# power-supply.net
KiCad netlist of a schematic drawn in Altium Designer
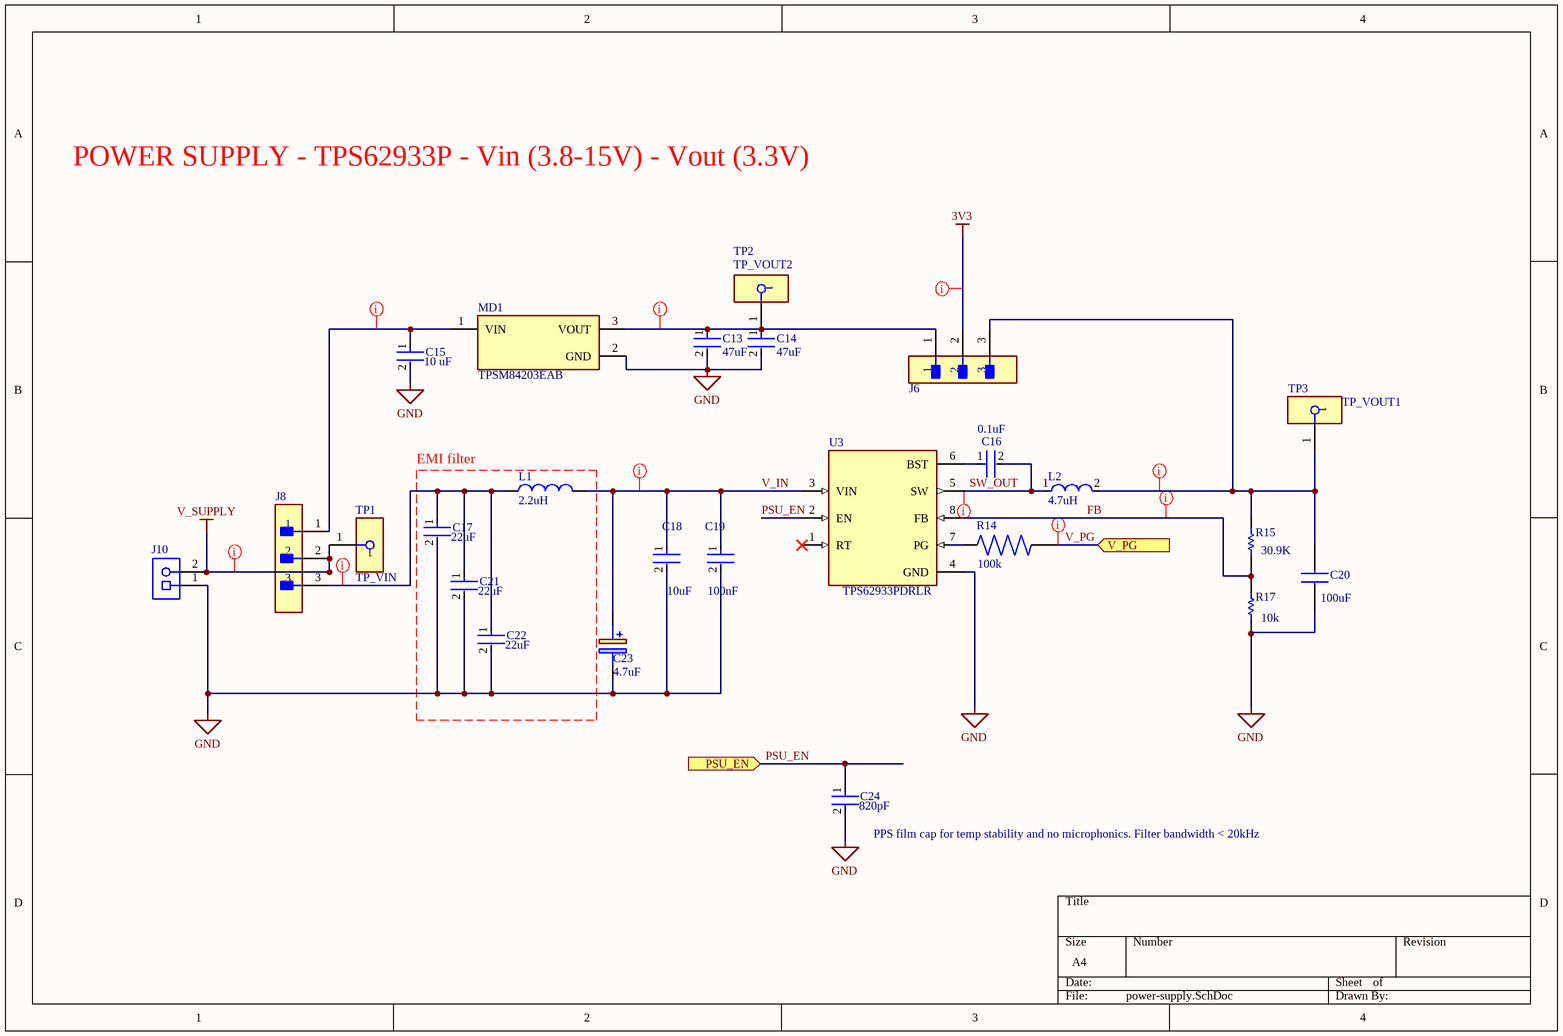
[diagram p0: power-supply.SchDoc]

(export (version "E")
  (design (tool "Eeschema 10.0.6"))
  (components
    (comp (ref "C13")
      (value "47uF")
      (footprint "FP-C3216-160-0_2-MFG")
      (description "Multilayer Ceramic Capacitors 47uF ±20% 25V X5R SMD 1206")
      (fields (field (name "VOLTAGE") "25V") (field (name "TOLERANCE") "20%"))
      (libsource (lib "Altium Content Vault") (part "11868f565c42a9108669ba33697ecf6"))
    )
    (comp (ref "C14")
      (value "47uF")
      (footprint "FP-C3216-160-0_2-MFG")
      (description "Multilayer Ceramic Capacitors 47uF ±20% 25V X5R SMD 1206")
      (fields (field (name "VOLTAGE") "25V") (field (name "TOLERANCE") "20%"))
      (libsource (lib "Altium Content Vault") (part "11868f565c42a9108669ba33697ecf6"))
    )
    (comp (ref "C15")
      (value "10 uF")
      (footprint "FP-GRT31C-0_2-IPC_A")
      (description "Multi-Layer Ceramic Capacitor 10uF 50V X5R ±10% 1206 Emboss T/R")
      (fields (field (name "TOLERANCE") "10%"))
      (libsource (lib "Altium Content Vault") (part "02cd4be3c70576c341d710602a673aa"))
    )
    (comp (ref "C16")
      (value "0.1uF")
      (footprint "FP-C0603C104Z4VACTU-MFG")
      (description "CAP CER 0.1UF 16V Y5V 0603")
      (fields (field (name "TOLERANCE") "80%"))
      (libsource (lib "Altium Content Vault") (part "b4654b650e69147ec39a6b967a45e02"))
    )
    (comp (ref "C17")
      (value "22uF")
      (footprint "FP-GRM32-MFG")
      (description "CAP CER 22UF 25V X5R 1210")
      (fields
        (field (name "TOLERANCE") "10%")
        (field (name "MANUFACTURER") "Murata Electronics North America")
      )
      (libsource (lib "Altium Content Vault") (part "11868f565c42a9108669ba33697ecf6"))
    )
    (comp (ref "C18")
      (value "10uF")
      (footprint "FP-GRM21B-0_15-IPC_A")
      (description "Chip Multilayer Ceramic Capacitors for General Purpose, 0805, 10uF, X5R, 15%, 20%, 25V")
      (fields (field (name "TOLERANCE") "20%"))
      (libsource (lib "Altium Content Vault") (part "b4654b650e69147ec39a6b967a45e02"))
    )
    (comp (ref "C19")
      (value "100nF")
      (footprint "FP-0603-L_1_6_0_15-W_0_81-MFG")
      (description "General Purpose Ceramic Capacitor, 0603, 100nF, 10%, X7R, 15%, 25V")
      (fields (field (name "VOLTAGE") "25V") (field (name "TOLERANCE") "10%"))
      (libsource (lib "Altium Content Vault") (part "02cd4be3c70576c341d710602a673aa"))
    )
    (comp (ref "C20")
      (value "100uF")
      (footprint "CAPC3225X270N")
      (fields
        (field (name "MOUSER PART NUMBER") "81-GRM32EC80J107ME0L")
        (field (name "MANUFACTURER_PART_NUMBER") "GRM32EC80J107ME20L")
      )
      (libsource (lib "GRM32EC80J107ME20L") (part "GRM32EC80J107ME20L"))
    )
    (comp (ref "C21")
      (value "22uF")
      (footprint "FP-GRM32-MFG")
      (description "CAP CER 22UF 25V X5R 1210")
      (fields
        (field (name "TOLERANCE") "10%")
        (field (name "MANUFACTURER") "Murata Electronics North America")
      )
      (libsource (lib "Altium Content Vault") (part "11868f565c42a9108669ba33697ecf6"))
    )
    (comp (ref "C22")
      (value "22uF")
      (footprint "FP-GRM32-MFG")
      (description "CAP CER 22UF 25V X5R 1210")
      (fields
        (field (name "TOLERANCE") "10%")
        (field (name "MANUFACTURER") "Murata Electronics North America")
      )
      (libsource (lib "Altium Content Vault") (part "11868f565c42a9108669ba33697ecf6"))
    )
    (comp (ref "C23")
      (value "4.7uF")
      (footprint "CAPPM3528X120N")
      (description "Cap Tant Solid 4.7uF 35V B CASE 10% (3.5 X 2.8 X 1.9mm) Inward L SMD 3528-21 0.7 Ohm 125C T/R")
      (fields
        (field (name "MOUSER PART NUMBER") "581-TPSB475K035R0700")
        (field (name "MANUFACTURER_PART_NUMBER") "TPSB475K035R0700")
      )
      (libsource (lib "TPSB475K035R0700") (part "TPSB475K035R0700"))
    )
    (comp (ref "C24")
      (value "ECH-U1H821JX5")
      (footprint "FP-ECHUJ1-MFG")
      (description "CAP FILM 820PF 5% 50VDC 0805")
      (fields
        (field (name "TOLERANCE") "5%")
        (field (name "CAPACITANCE") "820pF")
        (field (name "VOLTAGE") "50V")
      )
      (libsource (lib "Altium Content Vault") (part "b4654b650e69147ec39a6b967a45e02"))
    )
    (comp (ref "J6")
      (value "PREC003SAAN-RC")
      (footprint "FP-PREC003SAAN-RC-MFG")
      (description "PREC003SAAN-RC Conn Header Vert 3POS 2.54MM")
      (libsource (lib "Altium Content Vault") (part "0d3f023dd272f625e17a2be33dea85f"))
    )
    (comp (ref "J8")
      (value "PREC003SAAN-RC")
      (footprint "FP-PREC003SAAN-RC-MFG")
      (description "PREC003SAAN-RC Conn Header Vert 3POS 2.54MM")
      (libsource (lib "") (part "0d3f023dd272f625e17a2be33dea85f_1"))
    )
    (comp (ref "J10")
      (value "1729128")
      (footprint "PHOE-1729128-2_V")
      (description "PCB Terminal Block, 13.5 A, 400 V, 2-Pin THD, RoHS, Bulk")
      (fields (field (name "MANUFACTURER") "Phoenix Contact"))
      (libsource (lib "Altium Content Vault") (part "CN-2P-F-R2"))
    )
    (comp (ref "L1")
      (value "2.2uH")
      (footprint "WE-PMCI_1210_L3.2W2.5H1.2")
      (description "74479299222 General Purpose Inductor, 2.2uH, 15%, 1 Element, Iron Alloy-Core, SMD, 1210")
      (fields (field (name "TOLERANCE") "20%"))
      (libsource (lib "Altium Content Vault") (part "Inductor - 1"))
    )
    (comp (ref "L2")
      (value "4.7uH")
      (footprint "FP-IHLP-3232DZ-FP_2_413x5-MFG")
      (description "Commercial Inductors, Low DCR Series 4.7uH 8A 22.6mΩ 20%")
      (fields (field (name "TOLERANCE") "20%"))
      (libsource (lib "Altium Content Vault") (part "725321dda6339637d4d059423bc1c3c"))
    )
    (comp (ref "MD1")
      (value "TPSM84203EAB")
      (footprint "FP-EAB0003A-MFG")
      (description "DC DC CONVERTER 3.3V")
      (libsource (lib "Altium Content Vault") (part "495afe2ae4e3f912dabcd063790f0cb"))
    )
    (comp (ref "R14")
      (value "100k")
      (footprint "RESC1508X50N")
      (fields (field (name "MF") "Vishay") (field (name "MP") "CRCW0603100KFKEA"))
      (libsource (lib "CRCW0603100KFKEA") (part "CRCW0603100KFKEA"))
    )
    (comp (ref "R15")
      (value "30.9K")
      (footprint "RESC1608X55X25NL10T15")
      (description "Rfbt")
      (fields (field (name "MANUFACTURER") "Yageo") (field (name "PART NUMBER") "RC0603FR-0730K9L"))
      (libsource (lib "Altium Content Vault") (part "RES"))
    )
    (comp (ref "R17")
      (value "10k")
      (footprint "RESC1609X50X30NL8T20")
      (fields (field (name "MANUFACTURER") "Vishay Semiconductor"))
      (libsource (lib "Altium Content Vault") (part "RES-2"))
    )
    (comp (ref "TP1")
      (value "TP_VIN")
      (footprint "FP-5019-MFG")
      (description "V_IN_TEST")
      (libsource (lib "Altium Content Vault") (part "98815daf2f2c152b0c43f5ab9800df6"))
    )
    (comp (ref "TP2")
      (value "TP_VOUT2")
      (footprint "FP-5019-MFG")
      (libsource (lib "") (part "98815daf2f2c152b0c43f5ab9800df6_1"))
    )
    (comp (ref "TP3")
      (value "TP_VOUT1")
      (footprint "FP-5019-MFG")
      (libsource (lib "") (part "98815daf2f2c152b0c43f5ab9800df6_1"))
    )
    (comp (ref "U3")
      (value "TPS62933PDRLR")
      (footprint "SOFL50P160X60-8S")
      (libsource (lib "TPS62933PDRLR") (part "TPS62933PDRLR"))
    )
  )
  (nets
    (net (code "1") (name "/FB") (class "Default")
      (node (ref "R15") (pin "1") (pinfunction "1_1") (pintype "passive"))
      (node (ref "R17") (pin "2") (pinfunction "2_2") (pintype "passive"))
      (node (ref "U3") (pin "8") (pinfunction "FB_8") (pintype "input"))
    )
    (net (code "2") (name "/PSU_EN") (class "Default")
      (node (ref "C24") (pin "1") (pinfunction "1_1") (pintype "passive"))
      (node (ref "U3") (pin "2") (pinfunction "EN_2") (pintype "input"))
    )
    (net (code "3") (name "/SW_OUT") (class "Default")
      (node (ref "C16") (pin "2") (pinfunction "2_2") (pintype "passive"))
      (node (ref "L2") (pin "1") (pinfunction "1_1") (pintype "passive"))
      (node (ref "U3") (pin "5") (pinfunction "SW_5") (pintype "output"))
    )
    (net (code "4") (name "/V_IN") (class "Default")
      (node (ref "C18") (pin "1") (pinfunction "1_1") (pintype "passive"))
      (node (ref "C19") (pin "1") (pinfunction "1_1") (pintype "passive"))
      (node (ref "C23") (pin "1") (pinfunction "+_1") (pintype "passive"))
      (node (ref "L1") (pin "2") (pinfunction "2_2") (pintype "passive"))
      (node (ref "U3") (pin "3") (pinfunction "VIN_3") (pintype "input"))
    )
    (net (code "5") (name "/V_PG") (class "Default")
      (node (ref "R14") (pin "2") (pinfunction "2_2") (pintype "passive"))
    )
    (net (code "6") (name "3V3") (class "Default")
      (node (ref "J6") (pin "2") (pinfunction "2_2") (pintype "passive"))
    )
    (net (code "7") (name "GND") (class "Default")
      (node (ref "C13") (pin "2") (pinfunction "2_2") (pintype "passive"))
      (node (ref "C14") (pin "2") (pinfunction "2_2") (pintype "passive"))
      (node (ref "C15") (pin "2") (pinfunction "2_2") (pintype "passive"))
      (node (ref "C17") (pin "2") (pinfunction "2_2") (pintype "passive"))
      (node (ref "C18") (pin "2") (pinfunction "2_2") (pintype "passive"))
      (node (ref "C19") (pin "2") (pinfunction "2_2") (pintype "passive"))
      (node (ref "C20") (pin "1") (pinfunction "1_1") (pintype "passive"))
      (node (ref "C21") (pin "2") (pinfunction "2_2") (pintype "passive"))
      (node (ref "C22") (pin "2") (pinfunction "2_2") (pintype "passive"))
      (node (ref "C23") (pin "2") (pinfunction "-_2") (pintype "passive"))
      (node (ref "C24") (pin "2") (pinfunction "2_2") (pintype "passive"))
      (node (ref "J10") (pin "1") (pinfunction "1_1") (pintype "passive"))
      (node (ref "MD1") (pin "2") (pinfunction "GND_2") (pintype "power_in"))
      (node (ref "R17") (pin "1") (pinfunction "1_1") (pintype "passive"))
      (node (ref "U3") (pin "4") (pinfunction "GND_4") (pintype "power_in"))
    )
    (net (code "8") (name "Net-(C17-Pad1)") (class "Default")
      (node (ref "C17") (pin "1") (pinfunction "1_1") (pintype "passive"))
      (node (ref "C21") (pin "1") (pinfunction "1_1") (pintype "passive"))
      (node (ref "C22") (pin "1") (pinfunction "1_1") (pintype "passive"))
      (node (ref "J8") (pin "3") (pinfunction "3_3") (pintype "passive"))
      (node (ref "L1") (pin "1") (pinfunction "1_1") (pintype "passive"))
    )
    (net (code "9") (name "Net-(C20-Pad2)") (class "Default")
      (node (ref "C20") (pin "2") (pinfunction "2_2") (pintype "passive"))
      (node (ref "J6") (pin "3") (pinfunction "3_3") (pintype "passive"))
      (node (ref "L2") (pin "2") (pinfunction "2_2") (pintype "passive"))
      (node (ref "R15") (pin "2") (pinfunction "2_2") (pintype "passive"))
      (node (ref "TP3") (pin "1") (pinfunction "1_1") (pintype "passive"))
    )
    (net (code "10") (name "Net-(MD1-VIN)") (class "Default")
      (node (ref "C15") (pin "1") (pinfunction "1_1") (pintype "passive"))
      (node (ref "J8") (pin "1") (pinfunction "1_1") (pintype "passive"))
      (node (ref "MD1") (pin "1") (pinfunction "VIN_1") (pintype "power_in"))
    )
    (net (code "11") (name "Net-(MD1-VOUT)") (class "Default")
      (node (ref "C13") (pin "1") (pinfunction "1_1") (pintype "passive"))
      (node (ref "C14") (pin "1") (pinfunction "1_1") (pintype "passive"))
      (node (ref "J6") (pin "1") (pinfunction "1_1") (pintype "passive"))
      (node (ref "MD1") (pin "3") (pinfunction "VOUT_3") (pintype "power_in"))
      (node (ref "TP2") (pin "1") (pinfunction "1_1") (pintype "passive"))
    )
    (net (code "12") (name "Net-(U3-BST)") (class "Default")
      (node (ref "C16") (pin "1") (pinfunction "1_1") (pintype "passive"))
      (node (ref "U3") (pin "6") (pinfunction "BST_6") (pintype "power_in"))
    )
    (net (code "13") (name "Net-(U3-PG)") (class "Default")
      (node (ref "R14") (pin "1") (pinfunction "1_1") (pintype "passive"))
      (node (ref "U3") (pin "7") (pinfunction "PG_7") (pintype "input"))
    )
    (net (code "14") (name "V_SUPPLY") (class "Default")
      (node (ref "J10") (pin "2") (pinfunction "2_2") (pintype "passive"))
      (node (ref "J8") (pin "2") (pinfunction "2_2") (pintype "passive"))
      (node (ref "TP1") (pin "1") (pinfunction "1_1") (pintype "passive"))
    )
    (net (code "15") (name "unconnected-(U3-RT-Pad1)") (class "Default")
      (node (ref "U3") (pin "1") (pinfunction "RT_1") (pintype "input+no_connect"))
    )
  )
)
